# Cyusb3014_-_1.net
KiCad netlist of a schematic drawn in Altium Designer
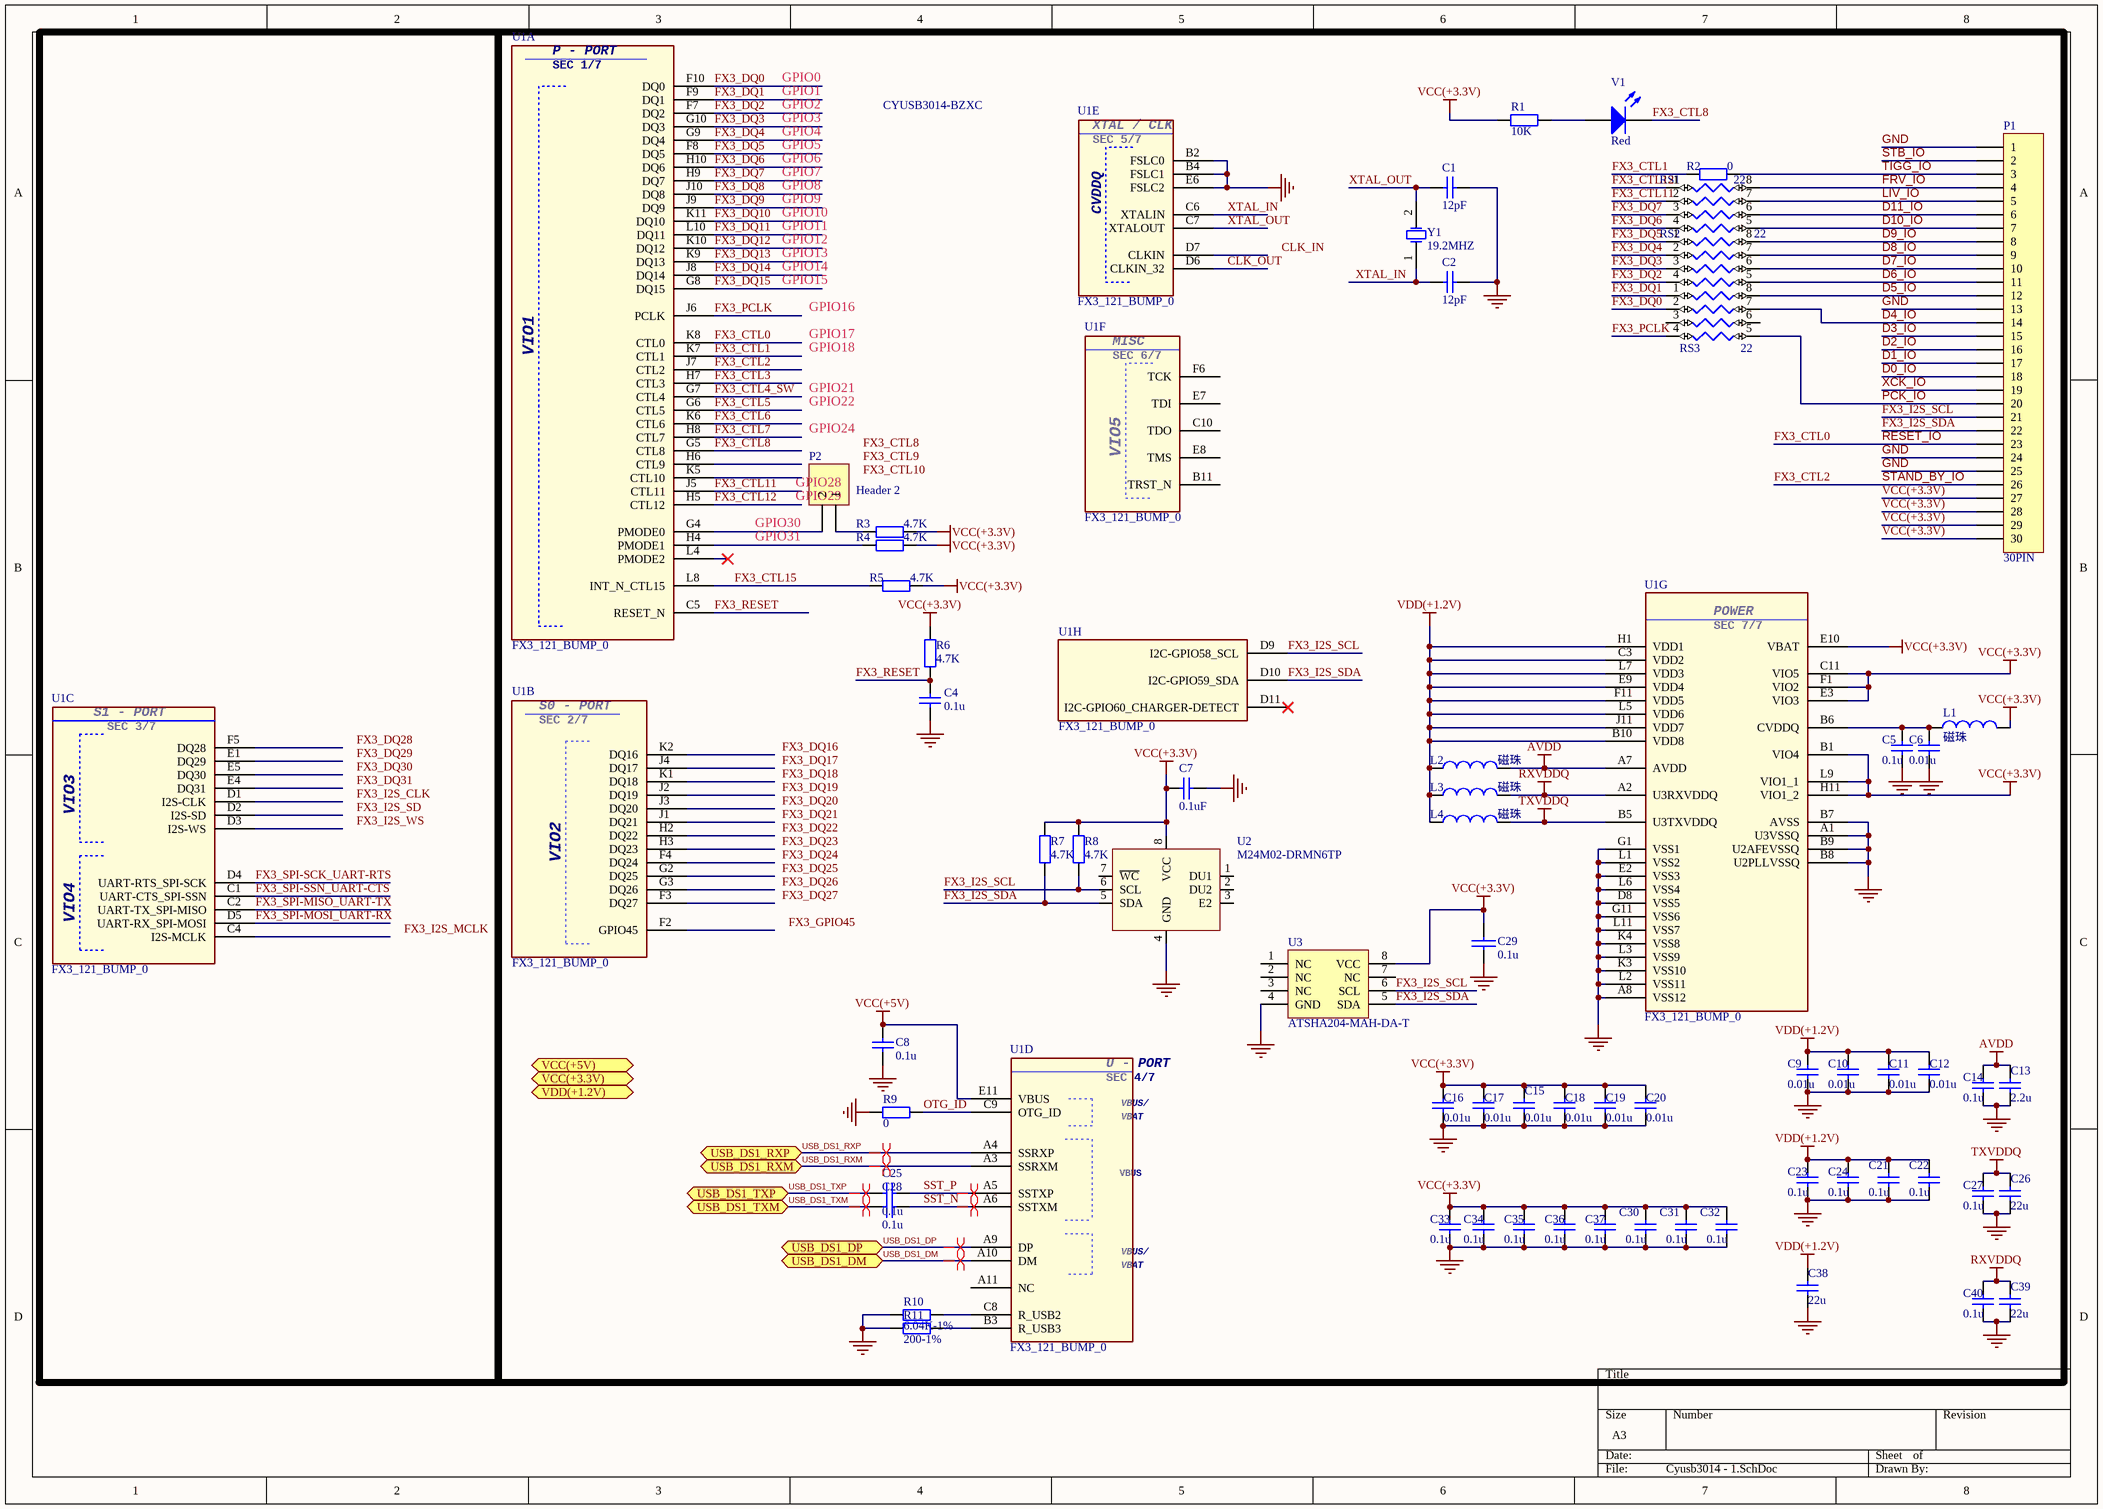
[diagram p0: Cyusb3014 - 1.SchDoc]

(export (version "E")
  (design (tool "Eeschema 10.0.6"))
  (components
    (comp (ref "C1")
      (value "12pF")
      (footprint "0603S-CAP")
      (description "CAP CER SMT 4.3pF 0805")
      (fields
        (field (name "2. MANUFACTURERE PART NUMBER") "C0805C439D5GACTU")
        (field (name "8. ALTERNATE PART") "any")
      )
      (libsource (lib "Peeple_eval") (part "CAP CER SMT 4.3pF 0805"))
    )
    (comp (ref "C2")
      (value "12pF")
      (footprint "0603S-CAP")
      (description "CAP CER SMT 4.3pF 0805")
      (fields
        (field (name "2. MANUFACTURERE PART NUMBER") "C0805C439D5GACTU")
        (field (name "8. ALTERNATE PART") "any")
      )
      (libsource (lib "Peeple_eval") (part "CAP CER SMT 4.3pF 0805"))
    )
    (comp (ref "C4")
      (value "0.1u")
      (footprint "0603S-CAP")
      (description "50V/8.2u/0805")
      (fields (field (name "PUBLISHER") "Altium Limited"))
      (libsource (lib "Miscellaneous Devices") (part "Cap"))
    )
    (comp (ref "C5")
      (value "0.1u")
      (footprint "C0402")
      (description "Capacitor")
      (fields (field (name "PUBLISHER") "Altium Limited"))
      (libsource (lib "WM360") (part "CAP0805"))
    )
    (comp (ref "C6")
      (value "0.01u")
      (footprint "C0402")
      (description "Capacitor")
      (fields (field (name "PUBLISHER") "Altium Limited"))
      (libsource (lib "WM360") (part "CAP0805"))
    )
    (comp (ref "C7")
      (value "0.1uF")
      (footprint "0603S-CAP")
      (description "CAP SMT 0.1uF 16V X7R")
      (fields
        (field (name "2. MANUFACTURERE PART NUMBER") "C0805C104K4RACTU")
        (field (name "8. ALTERNATE PART") "any")
      )
      (libsource (lib "Peeple_eval") (part "CAP SMT 0.1uF 16V X7R"))
    )
    (comp (ref "C8")
      (value "0.1u")
      (footprint "C0402")
      (description "Capacitor")
      (fields (field (name "PUBLISHER") "Altium Limited"))
      (libsource (lib "WM360") (part "CAP0805"))
    )
    (comp (ref "C9")
      (value "0.01u")
      (footprint "C0402")
      (description "Capacitor")
      (fields (field (name "PUBLISHER") "Altium Limited"))
      (libsource (lib "WM360") (part "CAP0805"))
    )
    (comp (ref "C10")
      (value "0.01u")
      (footprint "C0402")
      (description "Capacitor")
      (fields (field (name "PUBLISHER") "Altium Limited"))
      (libsource (lib "WM360") (part "CAP0805"))
    )
    (comp (ref "C11")
      (value "0.01u")
      (footprint "C0402")
      (description "Capacitor")
      (fields (field (name "PUBLISHER") "Altium Limited"))
      (libsource (lib "WM360") (part "CAP0805"))
    )
    (comp (ref "C12")
      (value "0.01u")
      (footprint "C0402")
      (description "Capacitor")
      (fields (field (name "PUBLISHER") "Altium Limited"))
      (libsource (lib "WM360") (part "CAP0805"))
    )
    (comp (ref "C13")
      (value "2.2u")
      (footprint "C0805S-CAP")
      (description "Capacitor")
      (fields (field (name "PUBLISHER") "Altium Limited"))
      (libsource (lib "USB_CAMERA") (part "CAP0805"))
    )
    (comp (ref "C14")
      (value "0.1u")
      (footprint "C0402")
      (description "Capacitor")
      (fields (field (name "PUBLISHER") "Altium Limited"))
      (libsource (lib "WM360") (part "CAP0805"))
    )
    (comp (ref "C15")
      (value "0.01u")
      (footprint "C0402")
      (description "Capacitor")
      (fields (field (name "PUBLISHER") "Altium Limited"))
      (libsource (lib "WM360") (part "CAP0805"))
    )
    (comp (ref "C16")
      (value "0.01u")
      (footprint "C0402")
      (description "Capacitor")
      (fields (field (name "PUBLISHER") "Altium Limited"))
      (libsource (lib "WM360") (part "CAP0805"))
    )
    (comp (ref "C17")
      (value "0.01u")
      (footprint "C0402")
      (description "Capacitor")
      (fields (field (name "PUBLISHER") "Altium Limited"))
      (libsource (lib "WM360") (part "CAP0805"))
    )
    (comp (ref "C18")
      (value "0.01u")
      (footprint "C0402")
      (description "Capacitor")
      (fields (field (name "PUBLISHER") "Altium Limited"))
      (libsource (lib "WM360") (part "CAP0805"))
    )
    (comp (ref "C19")
      (value "0.01u")
      (footprint "C0402")
      (description "Capacitor")
      (fields (field (name "PUBLISHER") "Altium Limited"))
      (libsource (lib "WM360") (part "CAP0805"))
    )
    (comp (ref "C20")
      (value "0.01u")
      (footprint "C0402")
      (description "Capacitor")
      (fields (field (name "PUBLISHER") "Altium Limited"))
      (libsource (lib "WM360") (part "CAP0805"))
    )
    (comp (ref "C21")
      (value "0.1u")
      (footprint "C0402")
      (description "Capacitor")
      (fields (field (name "PUBLISHER") "Altium Limited"))
      (libsource (lib "WM360") (part "CAP0805"))
    )
    (comp (ref "C22")
      (value "0.1u")
      (footprint "C0402")
      (description "Capacitor")
      (fields (field (name "PUBLISHER") "Altium Limited"))
      (libsource (lib "WM360") (part "CAP0805"))
    )
    (comp (ref "C23")
      (value "0.1u")
      (footprint "C0402")
      (description "Capacitor")
      (fields (field (name "PUBLISHER") "Altium Limited"))
      (libsource (lib "WM360") (part "CAP0805"))
    )
    (comp (ref "C24")
      (value "0.1u")
      (footprint "C0402")
      (description "Capacitor")
      (fields (field (name "PUBLISHER") "Altium Limited"))
      (libsource (lib "WM360") (part "CAP0805"))
    )
    (comp (ref "C25")
      (value "0.1u")
      (footprint "C0402")
      (description "Capacitor")
      (fields (field (name "PUBLISHER") "Altium Limited"))
      (libsource (lib "WM360") (part "CAP0805"))
    )
    (comp (ref "C26")
      (value "22u")
      (footprint "C0805S-CAP")
      (description "Capacitor")
      (fields (field (name "PUBLISHER") "Altium Limited"))
      (libsource (lib "USB_CAMERA") (part "CAP0805"))
    )
    (comp (ref "C27")
      (value "0.1u")
      (footprint "C0402")
      (description "Capacitor")
      (fields (field (name "PUBLISHER") "Altium Limited"))
      (libsource (lib "WM360") (part "CAP0805"))
    )
    (comp (ref "C28")
      (value "0.1u")
      (footprint "C0402")
      (description "Capacitor")
      (fields (field (name "PUBLISHER") "Altium Limited"))
      (libsource (lib "WM360") (part "CAP0805"))
    )
    (comp (ref "C29")
      (value "0.1u")
      (footprint "0603S-CAP")
      (description "RC=1206")
      (libsource (lib "*") (part "CAP"))
    )
    (comp (ref "C30")
      (value "0.1u")
      (footprint "C0402")
      (description "Capacitor")
      (fields (field (name "PUBLISHER") "Altium Limited"))
      (libsource (lib "WM360") (part "CAP0805"))
    )
    (comp (ref "C31")
      (value "0.1u")
      (footprint "C0402")
      (description "Capacitor")
      (fields (field (name "PUBLISHER") "Altium Limited"))
      (libsource (lib "WM360") (part "CAP0805"))
    )
    (comp (ref "C32")
      (value "0.1u")
      (footprint "C0402")
      (description "Capacitor")
      (fields (field (name "PUBLISHER") "Altium Limited"))
      (libsource (lib "WM360") (part "CAP0805"))
    )
    (comp (ref "C33")
      (value "0.1u")
      (footprint "C0402")
      (description "Capacitor")
      (fields (field (name "PUBLISHER") "Altium Limited"))
      (libsource (lib "WM360") (part "CAP0805"))
    )
    (comp (ref "C34")
      (value "0.1u")
      (footprint "C0402")
      (description "Capacitor")
      (fields (field (name "PUBLISHER") "Altium Limited"))
      (libsource (lib "WM360") (part "CAP0805"))
    )
    (comp (ref "C35")
      (value "0.1u")
      (footprint "C0402")
      (description "Capacitor")
      (fields (field (name "PUBLISHER") "Altium Limited"))
      (libsource (lib "WM360") (part "CAP0805"))
    )
    (comp (ref "C36")
      (value "0.1u")
      (footprint "C0402")
      (description "Capacitor")
      (fields (field (name "PUBLISHER") "Altium Limited"))
      (libsource (lib "WM360") (part "CAP0805"))
    )
    (comp (ref "C37")
      (value "0.1u")
      (footprint "C0402")
      (description "Capacitor")
      (fields (field (name "PUBLISHER") "Altium Limited"))
      (libsource (lib "WM360") (part "CAP0805"))
    )
    (comp (ref "C38")
      (value "22u")
      (footprint "C0805S-CAP")
      (description "Capacitor")
      (fields (field (name "PUBLISHER") "Altium Limited"))
      (libsource (lib "USB_CAMERA") (part "CAP0805"))
    )
    (comp (ref "C39")
      (value "22u")
      (footprint "C0805S-CAP")
      (description "Capacitor")
      (fields (field (name "PUBLISHER") "Altium Limited"))
      (libsource (lib "USB_CAMERA") (part "CAP0805"))
    )
    (comp (ref "C40")
      (value "0.1u")
      (footprint "C0402")
      (description "Capacitor")
      (fields (field (name "PUBLISHER") "Altium Limited"))
      (libsource (lib "WM360") (part "CAP0805"))
    )
    (comp (ref "L1")
      (value "磁珠")
      (footprint "L0603")
      (description "Inductor")
      (fields (field (name "PUBLISHER") "Altium Limited"))
      (libsource (lib "Miscellaneous Devices") (part "Inductor"))
    )
    (comp (ref "L2")
      (value "磁珠")
      (footprint "L0603")
      (description "Inductor")
      (fields (field (name "PUBLISHER") "Altium Limited"))
      (libsource (lib "Miscellaneous Devices") (part "Inductor"))
    )
    (comp (ref "L3")
      (value "磁珠")
      (footprint "L0603")
      (description "Inductor")
      (fields (field (name "PUBLISHER") "Altium Limited"))
      (libsource (lib "Miscellaneous Devices") (part "Inductor"))
    )
    (comp (ref "L4")
      (value "磁珠")
      (footprint "L0603")
      (description "Inductor")
      (fields (field (name "PUBLISHER") "Altium Limited"))
      (libsource (lib "Miscellaneous Devices") (part "Inductor"))
    )
    (comp (ref "P1")
      (value "30PIN")
      (footprint "FH12-30S-0.5SH")
      (description "Header, 30-Pin")
      (fields (field (name "PUBLISHER") "Altium Limited"))
      (libsource (lib "Miscellaneous Connectors") (part "Header 30"))
    )
    (comp (ref "P2")
      (value "Header 2")
      (footprint "HDR1X2")
      (description "Header, 2-Pin")
      (fields (field (name "PUBLISHER") "Altium Limited"))
      (libsource (lib "Miscellaneous Connectors") (part "Header 2"))
    )
    (comp (ref "R1")
      (value "10K")
      (footprint "0603S-RES")
      (description "Resistor")
      (fields (field (name "PUBLISHER") "Altium Limited"))
      (libsource (lib "") (part "Res2_1"))
    )
    (comp (ref "R2")
      (value "0")
      (footprint "0603S-RES")
      (description "Resistor")
      (fields (field (name "PUBLISHER") "Altium Limited"))
      (libsource (lib "") (part "Res2_1"))
    )
    (comp (ref "R3")
      (value "4.7K")
      (footprint "0603S-RES")
      (description "Resistor")
      (fields (field (name "PUBLISHER") "Altium Limited"))
      (libsource (lib "DM642") (part "Res2"))
    )
    (comp (ref "R4")
      (value "4.7K")
      (footprint "0603S-RES")
      (description "Resistor")
      (fields (field (name "PUBLISHER") "Altium Limited"))
      (libsource (lib "DM642") (part "Res2"))
    )
    (comp (ref "R5")
      (value "4.7K")
      (footprint "0603S-RES")
      (description "Resistor")
      (fields (field (name "PUBLISHER") "Altium Limited"))
      (libsource (lib "") (part "Res2_2"))
    )
    (comp (ref "R6")
      (value "4.7K")
      (footprint "0603S-RES")
      (description "Resistor")
      (fields (field (name "PUBLISHER") "Altium Limited"))
      (libsource (lib "") (part "Res2_3"))
    )
    (comp (ref "R7")
      (value "4.7K")
      (footprint "0603S-RES")
      (description "Resistor")
      (fields (field (name "PUBLISHER") "Altium Limited"))
      (libsource (lib "DM642") (part "Res2"))
    )
    (comp (ref "R8")
      (value "4.7K")
      (footprint "0603S-RES")
      (description "Resistor")
      (fields (field (name "PUBLISHER") "Altium Limited"))
      (libsource (lib "DM642") (part "Res2"))
    )
    (comp (ref "R9")
      (value "0")
      (footprint "0603S-RES")
      (description "Resistor")
      (fields (field (name "PUBLISHER") "Altium Limited"))
      (libsource (lib "") (part "Res2_2"))
    )
    (comp (ref "R10")
      (value "6.04K-1%")
      (footprint "0603S-RES")
      (description "Resistor")
      (fields (field (name "PUBLISHER") "Altium Limited"))
      (libsource (lib "") (part "Res2_2"))
    )
    (comp (ref "R11")
      (value "200-1%")
      (footprint "0603S-RES")
      (description "Resistor")
      (fields (field (name "PUBLISHER") "Altium Limited"))
      (libsource (lib "") (part "Res2_2"))
    )
    (comp (ref "RS1") (value "22") (footprint "NC06-4") (libsource (lib "*") (part "RN4")))
    (comp (ref "RS2") (value "22") (footprint "NC06-4") (libsource (lib "*") (part "RN4")))
    (comp (ref "RS3") (value "22") (footprint "NC06-4") (libsource (lib "*") (part "RN4")))
    (comp (ref "U1")
      (value "FX3_121_BUMP_0")
      (footprint "121_BGA_FX3")
      (libsource (lib "") (part "FX3_121_BUMP_0_1"))
    )
    (comp (ref "U2")
      (value "M24M02-DRMN6TP")
      (footprint "SOIC127P600X175-8N")
      (description "IC EEPROM 64KBIT 400KHZ 8SOIC")
      (fields
        (field (name "MANUFACTURER") "Microchip Technology")
        (field (name "MANUFACTURER PART NUMBER") "24LC64-I/SN")
      )
      (libsource (lib "Schlib1") (part "24LC64-I/SN"))
    )
    (comp (ref "U3")
      (value "ATSHA204-MAH-DA-T")
      (footprint "UDFN")
      (libsource (lib "CY7C68013-56") (part "AT24C128"))
    )
    (comp (ref "V1")
      (value "Red")
      (footprint "LED0805S")
      (description "Typical INFRARED GaAs LED")
      (fields (field (name "PUBLISHER") "Altium Limited"))
      (libsource (lib "DM642") (part "LED0"))
    )
    (comp (ref "Y1")
      (value "19.2MHZ")
      (footprint "爱普生晶振3.2×2.5MM - 无源")
      (description "Crystal, CRYSTAL 32.768KHZ 6PF SMD")
      (fields
        (field (name "2. MANUFACTURERE PART NUMBER") "ABS07-120-32.768KHZ-T")
        (field (name "4. SUPPLIER PART NUMBER") "535-11937-1-ND")
      )
      (libsource (lib "Peeple_eval") (part "XTAL 32.768KHZ"))
    )
  )
  (nets
    (net (code "2") (name "/CLK_OUT") (class "Default")
      (node (ref "U1") (pin "D6") (pinfunction "CLKIN_32_D6") (pintype "passive"))
    )
    (net (code "3") (name "/D0_IO") (class "Default")
      (node (ref "P1") (pin "18") (pinfunction "18_18") (pintype "passive"))
    )
    (net (code "4") (name "/D1_IO") (class "Default")
      (node (ref "P1") (pin "17") (pinfunction "17_17") (pintype "passive"))
    )
    (net (code "5") (name "/D2_IO") (class "Default")
      (node (ref "P1") (pin "16") (pinfunction "16_16") (pintype "passive"))
    )
    (net (code "6") (name "/D3_IO") (class "Default")
      (node (ref "P1") (pin "15") (pinfunction "15_15") (pintype "passive"))
    )
    (net (code "7") (name "/D4_IO") (class "Default")
      (node (ref "P1") (pin "14") (pinfunction "14_14") (pintype "passive"))
      (node (ref "RS3") (pin "7") (pinfunction "7_7") (pintype "bidirectional"))
    )
    (net (code "8") (name "/D5_IO") (class "Default")
      (node (ref "P1") (pin "12") (pinfunction "12_12") (pintype "passive"))
      (node (ref "RS3") (pin "8") (pinfunction "8_8") (pintype "bidirectional"))
    )
    (net (code "9") (name "/D6_IO") (class "Default")
      (node (ref "P1") (pin "11") (pinfunction "11_11") (pintype "passive"))
      (node (ref "RS2") (pin "5") (pinfunction "5_5") (pintype "bidirectional"))
    )
    (net (code "10") (name "/D7_IO") (class "Default")
      (node (ref "P1") (pin "10") (pinfunction "10_10") (pintype "passive"))
      (node (ref "RS2") (pin "6") (pinfunction "6_6") (pintype "bidirectional"))
    )
    (net (code "11") (name "/D8_IO") (class "Default")
      (node (ref "P1") (pin "9") (pinfunction "9_9") (pintype "passive"))
      (node (ref "RS2") (pin "7") (pinfunction "7_7") (pintype "bidirectional"))
    )
    (net (code "12") (name "/D9_IO") (class "Default")
      (node (ref "P1") (pin "8") (pinfunction "8_8") (pintype "passive"))
      (node (ref "RS2") (pin "8") (pinfunction "8_8") (pintype "bidirectional"))
    )
    (net (code "13") (name "/D10_IO") (class "Default")
      (node (ref "P1") (pin "7") (pinfunction "7_7") (pintype "passive"))
      (node (ref "RS1") (pin "5") (pinfunction "5_5") (pintype "bidirectional"))
    )
    (net (code "14") (name "/D11_IO") (class "Default")
      (node (ref "P1") (pin "6") (pinfunction "6_6") (pintype "passive"))
      (node (ref "RS1") (pin "6") (pinfunction "6_6") (pintype "bidirectional"))
    )
    (net (code "15") (name "/FRV_IO") (class "Default")
      (node (ref "P1") (pin "4") (pinfunction "4_4") (pintype "passive"))
      (node (ref "RS1") (pin "8") (pinfunction "8_8") (pintype "bidirectional"))
    )
    (net (code "16") (name "/FX3_CTL0") (class "Default")
      (node (ref "P1") (pin "23") (pinfunction "23_23") (pintype "passive"))
      (node (ref "U1") (pin "K8") (pinfunction "CTL0_K8") (pintype "passive"))
    )
    (net (code "17") (name "/FX3_CTL1") (class "Default")
      (node (ref "R2") (pin "2") (pinfunction "2_2") (pintype "passive"))
      (node (ref "U1") (pin "K7") (pinfunction "CTL1_K7") (pintype "passive"))
    )
    (net (code "18") (name "/FX3_CTL2") (class "Default")
      (node (ref "P1") (pin "26") (pinfunction "26_26") (pintype "passive"))
      (node (ref "U1") (pin "J7") (pinfunction "CTL2_J7") (pintype "passive"))
    )
    (net (code "19") (name "/FX3_CTL3") (class "Default")
      (node (ref "U1") (pin "H7") (pinfunction "CTL3_H7") (pintype "passive"))
    )
    (net (code "20") (name "/FX3_CTL4_SW") (class "Default")
      (node (ref "U1") (pin "G7") (pinfunction "CTL4_G7") (pintype "passive"))
    )
    (net (code "21") (name "/FX3_CTL5") (class "Default")
      (node (ref "U1") (pin "G6") (pinfunction "CTL5_G6") (pintype "passive"))
    )
    (net (code "22") (name "/FX3_CTL6") (class "Default")
      (node (ref "U1") (pin "K6") (pinfunction "CTL6_K6") (pintype "passive"))
    )
    (net (code "23") (name "/FX3_CTL7") (class "Default")
      (node (ref "U1") (pin "H8") (pinfunction "CTL7_H8") (pintype "passive"))
    )
    (net (code "24") (name "/FX3_CTL8") (class "Default")
      (node (ref "U1") (pin "G5") (pinfunction "CTL8_G5") (pintype "passive"))
      (node (ref "V1") (pin "2") (pinfunction "K_2") (pintype "passive"))
    )
    (net (code "27") (name "/FX3_CTL11") (class "Default")
      (node (ref "RS1") (pin "2") (pinfunction "2_2") (pintype "bidirectional"))
      (node (ref "U1") (pin "J5") (pinfunction "CTL11_J5") (pintype "passive"))
    )
    (net (code "28") (name "/FX3_CTL12") (class "Default")
      (node (ref "RS1") (pin "1") (pinfunction "1_1") (pintype "bidirectional"))
      (node (ref "U1") (pin "H5") (pinfunction "CTL12_H5") (pintype "passive"))
    )
    (net (code "29") (name "/FX3_CTL15") (class "Default")
      (node (ref "R5") (pin "2") (pinfunction "2_2") (pintype "passive"))
      (node (ref "U1") (pin "L8") (pinfunction "INT_N_CTL15_L8") (pintype "passive"))
    )
    (net (code "30") (name "/FX3_DQ0") (class "Default")
      (node (ref "RS3") (pin "2") (pinfunction "2_2") (pintype "bidirectional"))
      (node (ref "U1") (pin "F10") (pinfunction "DQ0_F10") (pintype "passive"))
    )
    (net (code "31") (name "/FX3_DQ1") (class "Default")
      (node (ref "RS3") (pin "1") (pinfunction "1_1") (pintype "bidirectional"))
      (node (ref "U1") (pin "F9") (pinfunction "DQ1_F9") (pintype "passive"))
    )
    (net (code "32") (name "/FX3_DQ2") (class "Default")
      (node (ref "RS2") (pin "4") (pinfunction "4_4") (pintype "bidirectional"))
      (node (ref "U1") (pin "F7") (pinfunction "DQ2_F7") (pintype "passive"))
    )
    (net (code "33") (name "/FX3_DQ3") (class "Default")
      (node (ref "RS2") (pin "3") (pinfunction "3_3") (pintype "bidirectional"))
      (node (ref "U1") (pin "G10") (pinfunction "DQ3_G10") (pintype "passive"))
    )
    (net (code "34") (name "/FX3_DQ4") (class "Default")
      (node (ref "RS2") (pin "2") (pinfunction "2_2") (pintype "bidirectional"))
      (node (ref "U1") (pin "G9") (pinfunction "DQ4_G9") (pintype "passive"))
    )
    (net (code "35") (name "/FX3_DQ5") (class "Default")
      (node (ref "RS2") (pin "1") (pinfunction "1_1") (pintype "bidirectional"))
      (node (ref "U1") (pin "F8") (pinfunction "DQ5_F8") (pintype "passive"))
    )
    (net (code "36") (name "/FX3_DQ6") (class "Default")
      (node (ref "RS1") (pin "4") (pinfunction "4_4") (pintype "bidirectional"))
      (node (ref "U1") (pin "H10") (pinfunction "DQ6_H10") (pintype "passive"))
    )
    (net (code "37") (name "/FX3_DQ7") (class "Default")
      (node (ref "RS1") (pin "3") (pinfunction "3_3") (pintype "bidirectional"))
      (node (ref "U1") (pin "H9") (pinfunction "DQ7_H9") (pintype "passive"))
    )
    (net (code "38") (name "/FX3_DQ8") (class "Default")
      (node (ref "U1") (pin "J10") (pinfunction "DQ8_J10") (pintype "passive"))
    )
    (net (code "39") (name "/FX3_DQ9") (class "Default")
      (node (ref "U1") (pin "J9") (pinfunction "DQ9_J9") (pintype "passive"))
    )
    (net (code "40") (name "/FX3_DQ10") (class "Default")
      (node (ref "U1") (pin "K11") (pinfunction "DQ10_K11") (pintype "passive"))
    )
    (net (code "41") (name "/FX3_DQ11") (class "Default")
      (node (ref "U1") (pin "L10") (pinfunction "DQ11_L10") (pintype "passive"))
    )
    (net (code "42") (name "/FX3_DQ12") (class "Default")
      (node (ref "U1") (pin "K10") (pinfunction "DQ12_K10") (pintype "passive"))
    )
    (net (code "43") (name "/FX3_DQ13") (class "Default")
      (node (ref "U1") (pin "K9") (pinfunction "DQ13_K9") (pintype "passive"))
    )
    (net (code "44") (name "/FX3_DQ14") (class "Default")
      (node (ref "U1") (pin "J8") (pinfunction "DQ14_J8") (pintype "passive"))
    )
    (net (code "45") (name "/FX3_DQ15") (class "Default")
      (node (ref "U1") (pin "G8") (pinfunction "DQ15_G8") (pintype "passive"))
    )
    (net (code "65") (name "/FX3_I2S_SCL") (class "Default")
      (node (ref "P1") (pin "21") (pinfunction "21_21") (pintype "passive"))
      (node (ref "R8") (pin "1") (pinfunction "1_1") (pintype "passive"))
      (node (ref "U1") (pin "D9") (pinfunction "I2C-GPIO58_SCL_D9") (pintype "passive"))
      (node (ref "U2") (pin "6") (pinfunction "SCL_6") (pintype "passive"))
      (node (ref "U3") (pin "6") (pinfunction "SCL_6") (pintype "passive"))
    )
    (net (code "67") (name "/FX3_I2S_SDA") (class "Default")
      (node (ref "P1") (pin "22") (pinfunction "22_22") (pintype "passive"))
      (node (ref "R7") (pin "1") (pinfunction "1_1") (pintype "passive"))
      (node (ref "U1") (pin "D10") (pinfunction "I2C-GPIO59_SDA_D10") (pintype "passive"))
      (node (ref "U2") (pin "5") (pinfunction "SDA_5") (pintype "passive"))
      (node (ref "U3") (pin "5") (pinfunction "SDA_5") (pintype "passive"))
    )
    (net (code "69") (name "/FX3_PCLK") (class "Default")
      (node (ref "RS3") (pin "4") (pinfunction "4_4") (pintype "bidirectional"))
      (node (ref "U1") (pin "J6") (pinfunction "PCLK_J6") (pintype "passive"))
    )
    (net (code "70") (name "/FX3_RESET") (class "Default")
      (node (ref "C4") (pin "2") (pinfunction "2_2") (pintype "passive"))
      (node (ref "R6") (pin "2") (pinfunction "2_2") (pintype "passive"))
      (node (ref "U1") (pin "C5") (pinfunction "RESET_N_C5") (pintype "passive"))
    )
    (net (code "71") (name "/FX3_SPI-MISO_UART-TX") (class "Default")
      (node (ref "U1") (pin "C2") (pinfunction "UART-TX_SPI-MISO_C2") (pintype "passive"))
    )
    (net (code "72") (name "/FX3_SPI-MOSI_UART-RX") (class "Default")
      (node (ref "U1") (pin "D5") (pinfunction "UART-RX_SPI-MOSI_D5") (pintype "passive"))
    )
    (net (code "73") (name "/FX3_SPI-SCK_UART-RTS") (class "Default")
      (node (ref "U1") (pin "D4") (pinfunction "UART-RTS_SPI-SCK_D4") (pintype "passive"))
    )
    (net (code "74") (name "/FX3_SPI-SSN_UART-CTS") (class "Default")
      (node (ref "U1") (pin "C1") (pinfunction "UART-CTS_SPI-SSN_C1") (pintype "passive"))
    )
    (net (code "75") (name "/LIV_IO") (class "Default")
      (node (ref "P1") (pin "5") (pinfunction "5_5") (pintype "passive"))
      (node (ref "RS1") (pin "7") (pinfunction "7_7") (pintype "bidirectional"))
    )
    (net (code "76") (name "/OTG_ID") (class "Default")
      (node (ref "R9") (pin "1") (pinfunction "1_1") (pintype "passive"))
      (node (ref "U1") (pin "C9") (pinfunction "OTG_ID_C9") (pintype "passive"))
    )
    (net (code "77") (name "/PCK_IO") (class "Default")
      (node (ref "P1") (pin "20") (pinfunction "20_20") (pintype "passive"))
      (node (ref "RS3") (pin "5") (pinfunction "5_5") (pintype "bidirectional"))
    )
    (net (code "78") (name "/SST_N") (class "Default")
      (node (ref "C28") (pin "2") (pinfunction "2_2") (pintype "passive"))
      (node (ref "U1") (pin "A6") (pinfunction "SSTXM_A6") (pintype "passive"))
    )
    (net (code "79") (name "/SST_P") (class "Default")
      (node (ref "C25") (pin "2") (pinfunction "2_2") (pintype "passive"))
      (node (ref "U1") (pin "A5") (pinfunction "SSTXP_A5") (pintype "passive"))
    )
    (net (code "80") (name "/STB_IO") (class "Default")
      (node (ref "P1") (pin "2") (pinfunction "2_2") (pintype "passive"))
    )
    (net (code "81") (name "/TIGG_IO") (class "Default")
      (node (ref "P1") (pin "3") (pinfunction "3_3") (pintype "passive"))
      (node (ref "R2") (pin "1") (pinfunction "1_1") (pintype "passive"))
    )
    (net (code "82") (name "/USB_DS1_DM") (class "Default")
      (node (ref "U1") (pin "A10") (pinfunction "DM_A10") (pintype "passive"))
    )
    (net (code "83") (name "/USB_DS1_DP") (class "Default")
      (node (ref "U1") (pin "A9") (pinfunction "DP_A9") (pintype "passive"))
    )
    (net (code "84") (name "/USB_DS1_RXM") (class "Default")
      (node (ref "U1") (pin "A3") (pinfunction "SSRXM_A3") (pintype "passive"))
    )
    (net (code "85") (name "/USB_DS1_RXP") (class "Default")
      (node (ref "U1") (pin "A4") (pinfunction "SSRXP_A4") (pintype "passive"))
    )
    (net (code "86") (name "/USB_DS1_TXM") (class "Default")
      (node (ref "C28") (pin "1") (pinfunction "1_1") (pintype "passive"))
    )
    (net (code "87") (name "/USB_DS1_TXP") (class "Default")
      (node (ref "C25") (pin "1") (pinfunction "1_1") (pintype "passive"))
    )
    (net (code "88") (name "/XCK_IO") (class "Default")
      (node (ref "P1") (pin "19") (pinfunction "19_19") (pintype "passive"))
    )
    (net (code "89") (name "/XTAL_IN") (class "Default")
      (node (ref "C2") (pin "2") (pinfunction "2_2") (pintype "passive"))
      (node (ref "U1") (pin "C6") (pinfunction "XTALIN_C6") (pintype "passive"))
      (node (ref "Y1") (pin "1") (pinfunction "OSC1_1") (pintype "passive"))
    )
    (net (code "90") (name "/XTAL_OUT") (class "Default")
      (node (ref "C1") (pin "2") (pinfunction "2_2") (pintype "passive"))
      (node (ref "U1") (pin "C7") (pinfunction "XTALOUT_C7") (pintype "passive"))
      (node (ref "Y1") (pin "2") (pinfunction "OSC2_2") (pintype "passive"))
    )
    (net (code "91") (name "AVDD") (class "Default")
      (node (ref "C13") (pin "2") (pinfunction "2_2") (pintype "passive"))
      (node (ref "C14") (pin "1") (pinfunction "1_1") (pintype "passive"))
      (node (ref "L2") (pin "2") (pinfunction "2_2") (pintype "passive"))
      (node (ref "U1") (pin "A7") (pinfunction "AVDD_A7") (pintype "passive"))
    )
    (net (code "92") (name "GND") (class "Default")
      (node (ref "C1") (pin "1") (pinfunction "1_1") (pintype "passive"))
      (node (ref "C10") (pin "2") (pinfunction "2_2") (pintype "passive"))
      (node (ref "C11") (pin "2") (pinfunction "2_2") (pintype "passive"))
      (node (ref "C12") (pin "2") (pinfunction "2_2") (pintype "passive"))
      (node (ref "C13") (pin "1") (pinfunction "1_1") (pintype "passive"))
      (node (ref "C14") (pin "2") (pinfunction "2_2") (pintype "passive"))
      (node (ref "C15") (pin "2") (pinfunction "2_2") (pintype "passive"))
      (node (ref "C16") (pin "2") (pinfunction "2_2") (pintype "passive"))
      (node (ref "C17") (pin "2") (pinfunction "2_2") (pintype "passive"))
      (node (ref "C18") (pin "2") (pinfunction "2_2") (pintype "passive"))
      (node (ref "C19") (pin "2") (pinfunction "2_2") (pintype "passive"))
      (node (ref "C2") (pin "1") (pinfunction "1_1") (pintype "passive"))
      (node (ref "C20") (pin "2") (pinfunction "2_2") (pintype "passive"))
      (node (ref "C21") (pin "2") (pinfunction "2_2") (pintype "passive"))
      (node (ref "C22") (pin "2") (pinfunction "2_2") (pintype "passive"))
      (node (ref "C23") (pin "2") (pinfunction "2_2") (pintype "passive"))
      (node (ref "C24") (pin "2") (pinfunction "2_2") (pintype "passive"))
      (node (ref "C26") (pin "1") (pinfunction "1_1") (pintype "passive"))
      (node (ref "C27") (pin "2") (pinfunction "2_2") (pintype "passive"))
      (node (ref "C29") (pin "2") (pintype "passive"))
      (node (ref "C30") (pin "2") (pinfunction "2_2") (pintype "passive"))
      (node (ref "C31") (pin "2") (pinfunction "2_2") (pintype "passive"))
      (node (ref "C32") (pin "2") (pinfunction "2_2") (pintype "passive"))
      (node (ref "C33") (pin "2") (pinfunction "2_2") (pintype "passive"))
      (node (ref "C34") (pin "2") (pinfunction "2_2") (pintype "passive"))
      (node (ref "C35") (pin "2") (pinfunction "2_2") (pintype "passive"))
      (node (ref "C36") (pin "2") (pinfunction "2_2") (pintype "passive"))
      (node (ref "C37") (pin "2") (pinfunction "2_2") (pintype "passive"))
      (node (ref "C38") (pin "1") (pinfunction "1_1") (pintype "passive"))
      (node (ref "C39") (pin "1") (pinfunction "1_1") (pintype "passive"))
      (node (ref "C4") (pin "1") (pinfunction "1_1") (pintype "passive"))
      (node (ref "C40") (pin "2") (pinfunction "2_2") (pintype "passive"))
      (node (ref "C5") (pin "2") (pinfunction "2_2") (pintype "passive"))
      (node (ref "C6") (pin "2") (pinfunction "2_2") (pintype "passive"))
      (node (ref "C7") (pin "1") (pinfunction "1_1") (pintype "passive"))
      (node (ref "C8") (pin "2") (pinfunction "2_2") (pintype "passive"))
      (node (ref "C9") (pin "2") (pinfunction "2_2") (pintype "passive"))
      (node (ref "P1") (pin "1") (pinfunction "1_1") (pintype "passive"))
      (node (ref "P1") (pin "13") (pinfunction "13_13") (pintype "passive"))
      (node (ref "P1") (pin "24") (pinfunction "24_24") (pintype "passive"))
      (node (ref "P1") (pin "25") (pinfunction "25_25") (pintype "passive"))
      (node (ref "R10") (pin "2") (pinfunction "2_2") (pintype "passive"))
      (node (ref "R11") (pin "2") (pinfunction "2_2") (pintype "passive"))
      (node (ref "R9") (pin "2") (pinfunction "2_2") (pintype "passive"))
      (node (ref "U1") (pin "A1") (pinfunction "U3VSSQ_A1") (pintype "passive"))
      (node (ref "U1") (pin "A8") (pinfunction "VSS12_A8") (pintype "passive"))
      (node (ref "U1") (pin "B2") (pinfunction "FSLC0_B2") (pintype "passive"))
      (node (ref "U1") (pin "B4") (pinfunction "FSLC1_B4") (pintype "passive"))
      (node (ref "U1") (pin "B7") (pinfunction "AVSS_B7") (pintype "passive"))
      (node (ref "U1") (pin "B8") (pinfunction "U2PLLVSSQ_B8") (pintype "passive"))
      (node (ref "U1") (pin "B9") (pinfunction "U2AFEVSSQ_B9") (pintype "passive"))
      (node (ref "U1") (pin "D8") (pinfunction "VSS5_D8") (pintype "passive"))
      (node (ref "U1") (pin "E2") (pinfunction "VSS3_E2") (pintype "passive"))
      (node (ref "U1") (pin "E6") (pinfunction "FSLC2_E6") (pintype "passive"))
      (node (ref "U1") (pin "G1") (pinfunction "VSS1_G1") (pintype "passive"))
      (node (ref "U1") (pin "G11") (pinfunction "VSS6_G11") (pintype "passive"))
      (node (ref "U1") (pin "K3") (pinfunction "VSS10_K3") (pintype "passive"))
      (node (ref "U1") (pin "K4") (pinfunction "VSS8_K4") (pintype "passive"))
      (node (ref "U1") (pin "L1") (pinfunction "VSS2_L1") (pintype "passive"))
      (node (ref "U1") (pin "L11") (pinfunction "VSS7_L11") (pintype "passive"))
      (node (ref "U1") (pin "L2") (pinfunction "VSS11_L2") (pintype "passive"))
      (node (ref "U1") (pin "L3") (pinfunction "VSS9_L3") (pintype "passive"))
      (node (ref "U1") (pin "L6") (pinfunction "VSS4_L6") (pintype "passive"))
      (node (ref "U2") (pin "4") (pinfunction "GND_4") (pintype "passive"))
      (node (ref "U3") (pin "4") (pinfunction "GND_4") (pintype "passive"))
    )
    (net (code "93") (name "Net-(P2-Pad1)") (class "Default")
      (node (ref "P2") (pin "1") (pinfunction "1_1") (pintype "passive"))
      (node (ref "R3") (pin "1") (pinfunction "1_1") (pintype "passive"))
    )
    (net (code "94") (name "Net-(U1A-PMODE0)") (class "Default")
      (node (ref "P2") (pin "2") (pinfunction "2_2") (pintype "passive"))
      (node (ref "U1") (pin "G4") (pinfunction "PMODE0_G4") (pintype "passive"))
    )
    (net (code "95") (name "Net-(U1A-PMODE1)") (class "Default")
      (node (ref "R4") (pin "1") (pinfunction "1_1") (pintype "passive"))
      (node (ref "U1") (pin "H4") (pinfunction "PMODE1_H4") (pintype "passive"))
    )
    (net (code "96") (name "Net-(U1D-R_USB2)") (class "Default")
      (node (ref "R10") (pin "1") (pinfunction "1_1") (pintype "passive"))
      (node (ref "U1") (pin "C8") (pinfunction "R_USB2_C8") (pintype "passive"))
    )
    (net (code "97") (name "Net-(U1D-R_USB3)") (class "Default")
      (node (ref "R11") (pin "1") (pinfunction "1_1") (pintype "passive"))
      (node (ref "U1") (pin "B3") (pinfunction "R_USB3_B3") (pintype "passive"))
    )
    (net (code "98") (name "Net-(U1G-CVDDQ)") (class "Default")
      (node (ref "C5") (pin "1") (pinfunction "1_1") (pintype "passive"))
      (node (ref "C6") (pin "1") (pinfunction "1_1") (pintype "passive"))
      (node (ref "L1") (pin "1") (pinfunction "1_1") (pintype "passive"))
      (node (ref "U1") (pin "B6") (pinfunction "CVDDQ_B6") (pintype "passive"))
    )
    (net (code "99") (name "Net-(V1-A)") (class "Default")
      (node (ref "R1") (pin "1") (pinfunction "1_1") (pintype "passive"))
      (node (ref "V1") (pin "1") (pinfunction "A_1") (pintype "passive"))
    )
    (net (code "100") (name "RXVDDQ") (class "Default")
      (node (ref "C39") (pin "2") (pinfunction "2_2") (pintype "passive"))
      (node (ref "C40") (pin "1") (pinfunction "1_1") (pintype "passive"))
      (node (ref "L3") (pin "2") (pinfunction "2_2") (pintype "passive"))
      (node (ref "U1") (pin "A2") (pinfunction "U3RXVDDQ_A2") (pintype "passive"))
    )
    (net (code "101") (name "TXVDDQ") (class "Default")
      (node (ref "C26") (pin "2") (pinfunction "2_2") (pintype "passive"))
      (node (ref "C27") (pin "1") (pinfunction "1_1") (pintype "passive"))
      (node (ref "L4") (pin "2") (pinfunction "2_2") (pintype "passive"))
      (node (ref "U1") (pin "B5") (pinfunction "U3TXVDDQ_B5") (pintype "passive"))
    )
    (net (code "102") (name "VCC(+3.3V)") (class "Default")
      (node (ref "C15") (pin "1") (pinfunction "1_1") (pintype "passive"))
      (node (ref "C16") (pin "1") (pinfunction "1_1") (pintype "passive"))
      (node (ref "C17") (pin "1") (pinfunction "1_1") (pintype "passive"))
      (node (ref "C18") (pin "1") (pinfunction "1_1") (pintype "passive"))
      (node (ref "C19") (pin "1") (pinfunction "1_1") (pintype "passive"))
      (node (ref "C20") (pin "1") (pinfunction "1_1") (pintype "passive"))
      (node (ref "C29") (pin "1") (pintype "passive"))
      (node (ref "C30") (pin "1") (pinfunction "1_1") (pintype "passive"))
      (node (ref "C31") (pin "1") (pinfunction "1_1") (pintype "passive"))
      (node (ref "C32") (pin "1") (pinfunction "1_1") (pintype "passive"))
      (node (ref "C33") (pin "1") (pinfunction "1_1") (pintype "passive"))
      (node (ref "C34") (pin "1") (pinfunction "1_1") (pintype "passive"))
      (node (ref "C35") (pin "1") (pinfunction "1_1") (pintype "passive"))
      (node (ref "C36") (pin "1") (pinfunction "1_1") (pintype "passive"))
      (node (ref "C37") (pin "1") (pinfunction "1_1") (pintype "passive"))
      (node (ref "C7") (pin "2") (pinfunction "2_2") (pintype "passive"))
      (node (ref "L1") (pin "2") (pinfunction "2_2") (pintype "passive"))
      (node (ref "P1") (pin "27") (pinfunction "27_27") (pintype "passive"))
      (node (ref "P1") (pin "28") (pinfunction "28_28") (pintype "passive"))
      (node (ref "P1") (pin "29") (pinfunction "29_29") (pintype "passive"))
      (node (ref "P1") (pin "30") (pinfunction "30_30") (pintype "passive"))
      (node (ref "R1") (pin "2") (pinfunction "2_2") (pintype "passive"))
      (node (ref "R3") (pin "2") (pinfunction "2_2") (pintype "passive"))
      (node (ref "R4") (pin "2") (pinfunction "2_2") (pintype "passive"))
      (node (ref "R5") (pin "1") (pinfunction "1_1") (pintype "passive"))
      (node (ref "R6") (pin "1") (pinfunction "1_1") (pintype "passive"))
      (node (ref "R7") (pin "2") (pinfunction "2_2") (pintype "passive"))
      (node (ref "R8") (pin "2") (pinfunction "2_2") (pintype "passive"))
      (node (ref "U1") (pin "B1") (pinfunction "VIO4_B1") (pintype "passive"))
      (node (ref "U1") (pin "C11") (pinfunction "VIO5_C11") (pintype "passive"))
      (node (ref "U1") (pin "E10") (pinfunction "VBAT_E10") (pintype "passive"))
      (node (ref "U1") (pin "E3") (pinfunction "VIO3_E3") (pintype "passive"))
      (node (ref "U1") (pin "F1") (pinfunction "VIO2_F1") (pintype "passive"))
      (node (ref "U1") (pin "H11") (pinfunction "VIO1_2_H11") (pintype "passive"))
      (node (ref "U1") (pin "L9") (pinfunction "VIO1_1_L9") (pintype "passive"))
      (node (ref "U2") (pin "8") (pinfunction "VCC_8") (pintype "passive"))
      (node (ref "U3") (pin "8") (pinfunction "VCC_8") (pintype "passive"))
    )
    (net (code "103") (name "VCC(+5V)") (class "Default")
      (node (ref "C8") (pin "1") (pinfunction "1_1") (pintype "passive"))
      (node (ref "U1") (pin "E11") (pinfunction "VBUS_E11") (pintype "passive"))
    )
    (net (code "104") (name "VDD(+1.2V)") (class "Default")
      (node (ref "C10") (pin "1") (pinfunction "1_1") (pintype "passive"))
      (node (ref "C11") (pin "1") (pinfunction "1_1") (pintype "passive"))
      (node (ref "C12") (pin "1") (pinfunction "1_1") (pintype "passive"))
      (node (ref "C21") (pin "1") (pinfunction "1_1") (pintype "passive"))
      (node (ref "C22") (pin "1") (pinfunction "1_1") (pintype "passive"))
      (node (ref "C23") (pin "1") (pinfunction "1_1") (pintype "passive"))
      (node (ref "C24") (pin "1") (pinfunction "1_1") (pintype "passive"))
      (node (ref "C38") (pin "2") (pinfunction "2_2") (pintype "passive"))
      (node (ref "C9") (pin "1") (pinfunction "1_1") (pintype "passive"))
      (node (ref "L2") (pin "1") (pinfunction "1_1") (pintype "passive"))
      (node (ref "L3") (pin "1") (pinfunction "1_1") (pintype "passive"))
      (node (ref "L4") (pin "1") (pinfunction "1_1") (pintype "passive"))
      (node (ref "U1") (pin "B10") (pinfunction "VDD8_B10") (pintype "passive"))
      (node (ref "U1") (pin "C3") (pinfunction "VDD2_C3") (pintype "passive"))
      (node (ref "U1") (pin "E9") (pinfunction "VDD4_E9") (pintype "passive"))
      (node (ref "U1") (pin "F11") (pinfunction "VDD5_F11") (pintype "passive"))
      (node (ref "U1") (pin "H1") (pinfunction "VDD1_H1") (pintype "passive"))
      (node (ref "U1") (pin "J11") (pinfunction "VDD7_J11") (pintype "passive"))
      (node (ref "U1") (pin "L5") (pinfunction "VDD6_L5") (pintype "passive"))
      (node (ref "U1") (pin "L7") (pinfunction "VDD3_L7") (pintype "passive"))
    )
    (net (code "105") (name "unconnected-(RS3-Pad3)") (class "Default")
      (node (ref "RS3") (pin "3") (pinfunction "3_3") (pintype "bidirectional"))
    )
    (net (code "106") (name "unconnected-(RS3-Pad6)") (class "Default")
      (node (ref "RS3") (pin "6") (pinfunction "6_6") (pintype "bidirectional"))
    )
    (net (code "107") (name "unconnected-(U1A-CTL9-PadH6)") (class "Default")
      (node (ref "U1") (pin "H6") (pinfunction "CTL9_H6") (pintype "passive"))
    )
    (net (code "108") (name "unconnected-(U1A-CTL10-PadK5)") (class "Default")
      (node (ref "U1") (pin "K5") (pinfunction "CTL10_K5") (pintype "passive"))
    )
    (net (code "109") (name "unconnected-(U1A-PMODE2-PadL4)") (class "Default")
      (node (ref "U1") (pin "L4") (pinfunction "PMODE2_L4") (pintype "passive+no_connect"))
    )
    (net (code "110") (name "unconnected-(U1B-DQ16-PadK2)") (class "Default")
      (node (ref "U1") (pin "K2") (pinfunction "DQ16_K2") (pintype "passive"))
    )
    (net (code "111") (name "unconnected-(U1B-DQ17-PadJ4)") (class "Default")
      (node (ref "U1") (pin "J4") (pinfunction "DQ17_J4") (pintype "passive"))
    )
    (net (code "112") (name "unconnected-(U1B-DQ18-PadK1)") (class "Default")
      (node (ref "U1") (pin "K1") (pinfunction "DQ18_K1") (pintype "passive"))
    )
    (net (code "113") (name "unconnected-(U1B-DQ19-PadJ2)") (class "Default")
      (node (ref "U1") (pin "J2") (pinfunction "DQ19_J2") (pintype "passive"))
    )
    (net (code "114") (name "unconnected-(U1B-DQ20-PadJ3)") (class "Default")
      (node (ref "U1") (pin "J3") (pinfunction "DQ20_J3") (pintype "passive"))
    )
    (net (code "115") (name "unconnected-(U1B-DQ21-PadJ1)") (class "Default")
      (node (ref "U1") (pin "J1") (pinfunction "DQ21_J1") (pintype "passive"))
    )
    (net (code "116") (name "unconnected-(U1B-DQ22-PadH2)") (class "Default")
      (node (ref "U1") (pin "H2") (pinfunction "DQ22_H2") (pintype "passive"))
    )
    (net (code "117") (name "unconnected-(U1B-DQ23-PadH3)") (class "Default")
      (node (ref "U1") (pin "H3") (pinfunction "DQ23_H3") (pintype "passive"))
    )
    (net (code "118") (name "unconnected-(U1B-DQ24-PadF4)") (class "Default")
      (node (ref "U1") (pin "F4") (pinfunction "DQ24_F4") (pintype "passive"))
    )
    (net (code "119") (name "unconnected-(U1B-DQ25-PadG2)") (class "Default")
      (node (ref "U1") (pin "G2") (pinfunction "DQ25_G2") (pintype "passive"))
    )
    (net (code "120") (name "unconnected-(U1B-DQ26-PadG3)") (class "Default")
      (node (ref "U1") (pin "G3") (pinfunction "DQ26_G3") (pintype "passive"))
    )
    (net (code "121") (name "unconnected-(U1B-DQ27-PadF3)") (class "Default")
      (node (ref "U1") (pin "F3") (pinfunction "DQ27_F3") (pintype "passive"))
    )
    (net (code "122") (name "unconnected-(U1B-GPIO45-PadF2)") (class "Default")
      (node (ref "U1") (pin "F2") (pinfunction "GPIO45_F2") (pintype "passive"))
    )
    (net (code "123") (name "unconnected-(U1C-DQ28-PadF5)") (class "Default")
      (node (ref "U1") (pin "F5") (pinfunction "DQ28_F5") (pintype "passive"))
    )
    (net (code "124") (name "unconnected-(U1C-DQ29-PadE1)") (class "Default")
      (node (ref "U1") (pin "E1") (pinfunction "DQ29_E1") (pintype "passive"))
    )
    (net (code "125") (name "unconnected-(U1C-DQ30-PadE5)") (class "Default")
      (node (ref "U1") (pin "E5") (pinfunction "DQ30_E5") (pintype "passive"))
    )
    (net (code "126") (name "unconnected-(U1C-DQ31-PadE4)") (class "Default")
      (node (ref "U1") (pin "E4") (pinfunction "DQ31_E4") (pintype "passive"))
    )
    (net (code "127") (name "unconnected-(U1C-I2S-CLK-PadD1)") (class "Default")
      (node (ref "U1") (pin "D1") (pinfunction "I2S-CLK_D1") (pintype "passive"))
    )
    (net (code "128") (name "unconnected-(U1C-I2S-MCLK-PadC4)") (class "Default")
      (node (ref "U1") (pin "C4") (pinfunction "I2S-MCLK_C4") (pintype "passive"))
    )
    (net (code "129") (name "unconnected-(U1C-I2S-SD-PadD2)") (class "Default")
      (node (ref "U1") (pin "D2") (pinfunction "I2S-SD_D2") (pintype "passive"))
    )
    (net (code "130") (name "unconnected-(U1C-I2S-WS-PadD3)") (class "Default")
      (node (ref "U1") (pin "D3") (pinfunction "I2S-WS_D3") (pintype "passive"))
    )
    (net (code "131") (name "unconnected-(U1D-NC-PadA11)") (class "Default")
      (node (ref "U1") (pin "A11") (pinfunction "NC_A11") (pintype "passive"))
    )
    (net (code "132") (name "unconnected-(U1E-CLKIN-PadD7)") (class "Default")
      (node (ref "U1") (pin "D7") (pinfunction "CLKIN_D7") (pintype "passive"))
    )
    (net (code "133") (name "unconnected-(U1F-TCK-PadF6)") (class "Default")
      (node (ref "U1") (pin "F6") (pinfunction "TCK_F6") (pintype "passive"))
    )
    (net (code "134") (name "unconnected-(U1F-TDI-PadE7)") (class "Default")
      (node (ref "U1") (pin "E7") (pinfunction "TDI_E7") (pintype "passive"))
    )
    (net (code "135") (name "unconnected-(U1F-TDO-PadC10)") (class "Default")
      (node (ref "U1") (pin "C10") (pinfunction "TDO_C10") (pintype "passive"))
    )
    (net (code "136") (name "unconnected-(U1F-TMS-PadE8)") (class "Default")
      (node (ref "U1") (pin "E8") (pinfunction "TMS_E8") (pintype "passive"))
    )
    (net (code "137") (name "unconnected-(U1F-TRST_N-PadB11)") (class "Default")
      (node (ref "U1") (pin "B11") (pinfunction "TRST_N_B11") (pintype "passive"))
    )
    (net (code "138") (name "unconnected-(U1H-I2C-GPIO60_CHARGER-DETECT-PadD11)") (class "Default")
      (node (ref "U1") (pin "D11") (pinfunction "I2C-GPIO60_CHARGER-DETECT_D11") (pintype "passive+no_connect"))
    )
    (net (code "139") (name "unconnected-(U2-DU1-Pad1)") (class "Default")
      (node (ref "U2") (pin "1") (pinfunction "DU1_1") (pintype "passive"))
    )
    (net (code "140") (name "unconnected-(U2-DU2-Pad2)") (class "Default")
      (node (ref "U2") (pin "2") (pinfunction "DU2_2") (pintype "passive"))
    )
    (net (code "141") (name "unconnected-(U2-E2-Pad3)") (class "Default")
      (node (ref "U2") (pin "3") (pinfunction "E2_3") (pintype "passive"))
    )
    (net (code "142") (name "unconnected-(U2-~{WC}-Pad7)") (class "Default")
      (node (ref "U2") (pin "7") (pinfunction "~{WC}_7") (pintype "passive"))
    )
    (net (code "143") (name "unconnected-(U3-NC-Pad1)") (class "Default")
      (node (ref "U3") (pin "1") (pinfunction "NC_1") (pintype "passive"))
    )
    (net (code "144") (name "unconnected-(U3-NC-Pad2)") (class "Default")
      (node (ref "U3") (pin "2") (pinfunction "NC_2") (pintype "passive"))
    )
    (net (code "145") (name "unconnected-(U3-NC-Pad3)") (class "Default")
      (node (ref "U3") (pin "3") (pinfunction "NC_3") (pintype "passive"))
    )
    (net (code "146") (name "unconnected-(U3-NC-Pad7)") (class "Default")
      (node (ref "U3") (pin "7") (pinfunction "NC_7") (pintype "passive"))
    )
  )
)
